# PowerSupply.net
KiCad netlist of a schematic drawn in Altium Designer
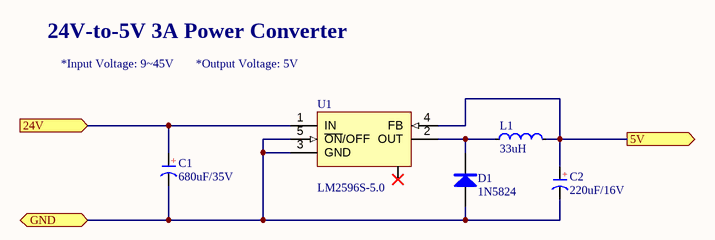
[diagram p0: PowerSupply.SchDoc]

(export (version "E")
  (design (tool "Eeschema 10.0.6"))
  (components
    (comp (ref "C1")
      (value "680uF/35V")
      (footprint "CM G(12.5*13.5)")
      (description "贴片电解电容 C542257")
      (fields (field (name "版权归属") "封装库来自淘宝 ID：黄晶宝石"))
      (libsource (lib "0.1 - 电阻-电容-电感") (part "CE_SMD"))
    )
    (comp (ref "C2")
      (value "220uF/16V")
      (footprint "CM D(6.3*7.7)")
      (description "贴片电解电容 C278407")
      (fields (field (name "版权归属") "封装库来自淘宝 ID：黄晶宝石"))
      (libsource (lib "0.1 - 电阻-电容-电感") (part "CE_SMD"))
    )
    (comp (ref "D1")
      (value "1N5824")
      (footprint "SMA")
      (description "整流二极管 C727065")
      (fields (field (name "版权归属") "封装库来自淘宝 ID：黄晶宝石"))
      (libsource (lib "0.2 - 二极管-整流桥") (part "M7"))
    )
    (comp (ref "L1")
      (value "InductanceSMD")
      (footprint "SMD-11.5x10.5")
      (description "C280568\r\n(MHCC10040-330M-R7)")
      (fields (field (name "INDUCTANCE") "33uH"))
      (libsource (lib "CustomizedComponents") (part "InductanceSMD"))
    )
    (comp (ref "U1")
      (value "LM2596S-5.0")
      (footprint "TO263-5A")
      (description "5V稳压芯片")
      (fields (field (name "PUBLISHER") "Altium Limited"))
      (libsource (lib "1.1 - 电源类芯片") (part "LM2596S-5.0"))
    )
  )
  (nets
    (net (code "1") (name "/5V") (class "Default")
      (node (ref "C2") (pin "1") (pinfunction "A_1") (pintype "passive"))
      (node (ref "L1") (pin "2") (pintype "passive"))
      (node (ref "U1") (pin "4") (pinfunction "FB_4") (pintype "input"))
    )
    (net (code "2") (name "/24V") (class "Default")
      (node (ref "C1") (pin "1") (pinfunction "A_1") (pintype "passive"))
      (node (ref "U1") (pin "1") (pinfunction "IN_1") (pintype "passive"))
    )
    (net (code "3") (name "/GND") (class "Default")
      (node (ref "C1") (pin "2") (pinfunction "K_2") (pintype "passive"))
      (node (ref "C2") (pin "2") (pinfunction "K_2") (pintype "passive"))
      (node (ref "D1") (pin "1") (pinfunction "A_1") (pintype "passive"))
      (node (ref "U1") (pin "3") (pinfunction "GND_3") (pintype "passive"))
      (node (ref "U1") (pin "5") (pinfunction "~{ON}/OFF_5") (pintype "input"))
    )
    (net (code "4") (name "Net-(D1-K)") (class "Default")
      (node (ref "D1") (pin "2") (pinfunction "K_2") (pintype "passive"))
      (node (ref "L1") (pin "1") (pintype "passive"))
      (node (ref "U1") (pin "2") (pinfunction "OUT_2") (pintype "power_in"))
    )
    (net (code "5") (name "unconnected-(U1-Pad6)") (class "Default")
      (node (ref "U1") (pin "6") (pinfunction "6_6") (pintype "power_in+no_connect"))
    )
  )
)
